# 8_-_DAC_and_MIC.net
KiCad netlist of a schematic drawn in Altium Designer
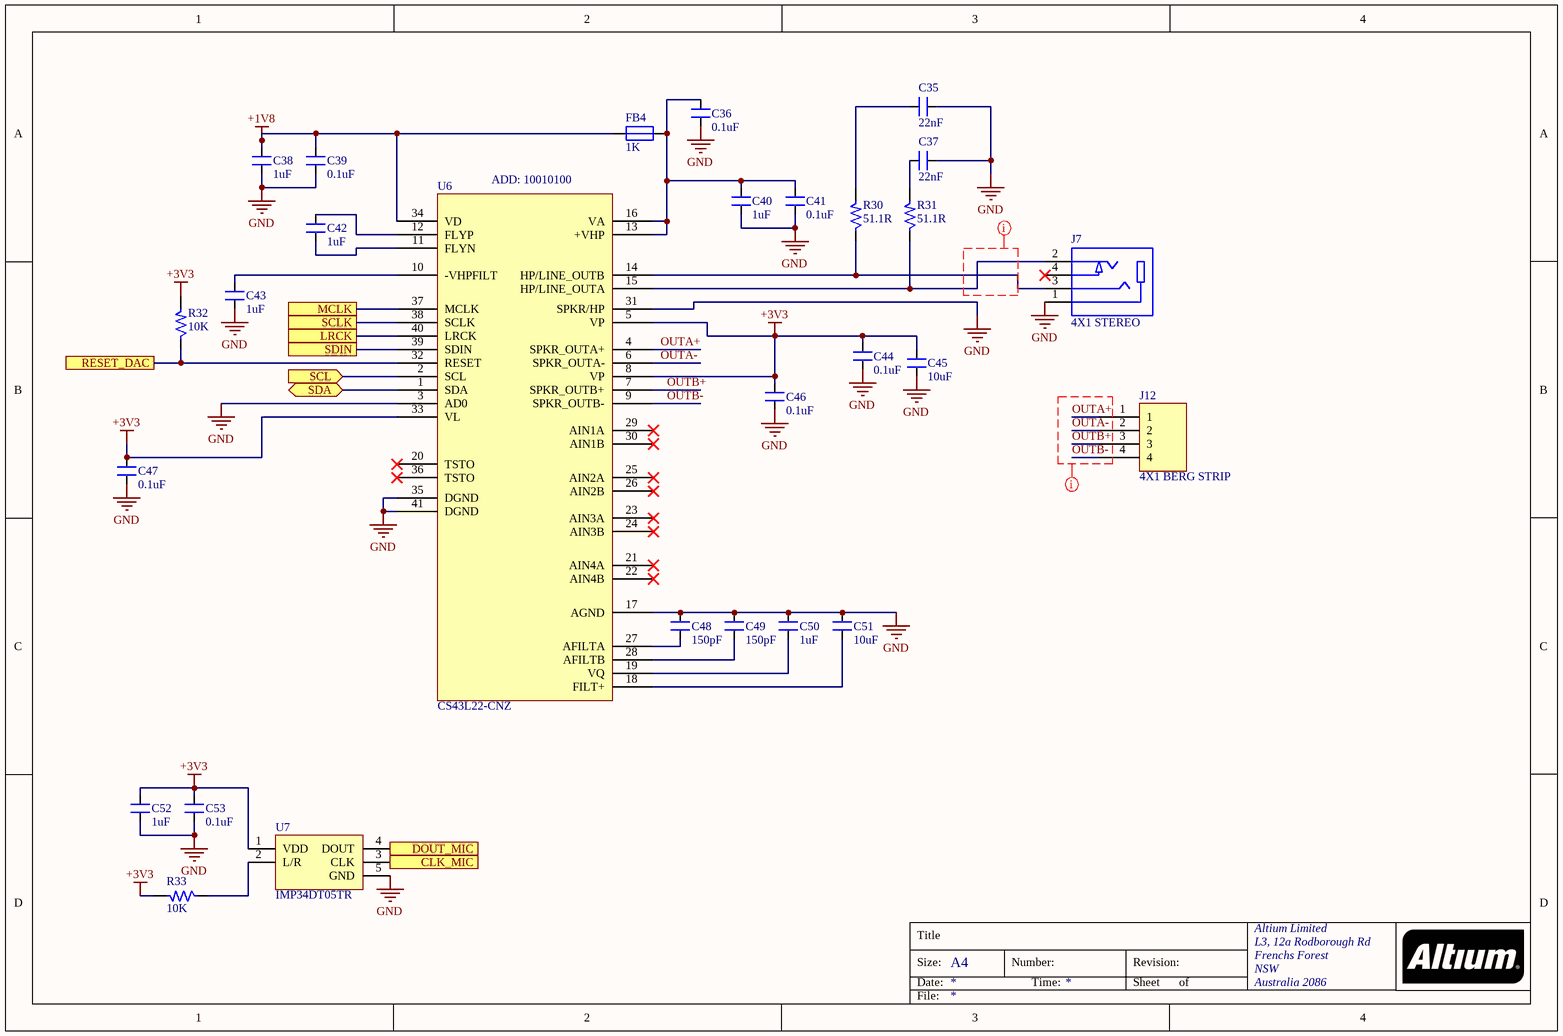
[diagram p0: [8] - DAC and MIC.SchDoc]

(export (version "E")
  (design (tool "Eeschema 10.0.6"))
  (components
    (comp (ref "C35")
      (value "22nF")
      (footprint "CAP_0805")
      (description "0.022µF ±10% 50V Ceramic Capacitor X7R 0805 (2012 Metric)")
      (fields
        (field (name "MANUFACTURER") "Samsung Electro-Mechanics")
        (field (name "MANUFACTURER PART NUMBER") "CL21B223KBANNNC")
      )
      (libsource (lib "ESTEEMPCBLIB") (part "CAP_22nF-50V-10%-0805"))
    )
    (comp (ref "C36")
      (value "0.1uF")
      (footprint "CAP_0805")
      (description "0.1µF ±10% 50V Ceramic Capacitor X7R 0805 (2012 Metric)")
      (fields
        (field (name "MANUFACTURER") "Samsung")
        (field (name "MANUFACTURER PART NUMBER") "CL21B104KBCNNNC")
      )
      (libsource (lib "ESTEEMPCBLIB") (part "CAP_0.1uF-50V-10%-0805"))
    )
    (comp (ref "C37")
      (value "22nF")
      (footprint "CAP_0805")
      (description "0.022µF ±10% 50V Ceramic Capacitor X7R 0805 (2012 Metric)")
      (fields
        (field (name "MANUFACTURER") "Samsung Electro-Mechanics")
        (field (name "MANUFACTURER PART NUMBER") "CL21B223KBANNNC")
      )
      (libsource (lib "ESTEEMPCBLIB") (part "CAP_22nF-50V-10%-0805"))
    )
    (comp (ref "C38")
      (value "1uF")
      (footprint "CAP_0805")
      (description "1µF ±5% 50V Ceramic Capacitor X7R 0805 (2012 Metric)")
      (fields
        (field (name "MANUFACTURER") "Samsung")
        (field (name "MANUFACTURER PART NUMBER") "CC0805JKX7R9BB105")
      )
      (libsource (lib "ESTEEMPCBLIB") (part "CAP_1uF-50V-5%-0805"))
    )
    (comp (ref "C39")
      (value "0.1uF")
      (footprint "CAP_0805")
      (description "0.1µF ±10% 50V Ceramic Capacitor X7R 0805 (2012 Metric)")
      (fields
        (field (name "MANUFACTURER") "Samsung")
        (field (name "MANUFACTURER PART NUMBER") "CL21B104KBCNNNC")
      )
      (libsource (lib "ESTEEMPCBLIB") (part "CAP_0.1uF-50V-10%-0805"))
    )
    (comp (ref "C40")
      (value "1uF")
      (footprint "CAP_0805")
      (description "1µF ±5% 50V Ceramic Capacitor X7R 0805 (2012 Metric)")
      (fields
        (field (name "MANUFACTURER") "Samsung")
        (field (name "MANUFACTURER PART NUMBER") "CC0805JKX7R9BB105")
      )
      (libsource (lib "ESTEEMPCBLIB") (part "CAP_1uF-50V-5%-0805"))
    )
    (comp (ref "C41")
      (value "0.1uF")
      (footprint "CAP_0805")
      (description "0.1µF ±10% 50V Ceramic Capacitor X7R 0805 (2012 Metric)")
      (fields
        (field (name "MANUFACTURER") "Samsung")
        (field (name "MANUFACTURER PART NUMBER") "CL21B104KBCNNNC")
      )
      (libsource (lib "ESTEEMPCBLIB") (part "CAP_0.1uF-50V-10%-0805"))
    )
    (comp (ref "C42")
      (value "1uF")
      (footprint "CAP_0805")
      (description "1µF ±5% 50V Ceramic Capacitor X7R 0805 (2012 Metric)")
      (fields
        (field (name "MANUFACTURER") "Samsung")
        (field (name "MANUFACTURER PART NUMBER") "CC0805JKX7R9BB105")
      )
      (libsource (lib "ESTEEMPCBLIB") (part "CAP_1uF-50V-5%-0805"))
    )
    (comp (ref "C43")
      (value "1uF")
      (footprint "CAP_0805")
      (description "1µF ±5% 50V Ceramic Capacitor X7R 0805 (2012 Metric)")
      (fields
        (field (name "MANUFACTURER") "Samsung")
        (field (name "MANUFACTURER PART NUMBER") "CC0805JKX7R9BB105")
      )
      (libsource (lib "ESTEEMPCBLIB") (part "CAP_1uF-50V-5%-0805"))
    )
    (comp (ref "C44")
      (value "0.1uF")
      (footprint "CAP_0805")
      (description "0.1µF ±10% 50V Ceramic Capacitor X7R 0805 (2012 Metric)")
      (fields
        (field (name "MANUFACTURER") "Samsung")
        (field (name "MANUFACTURER PART NUMBER") "CL21B104KBCNNNC")
      )
      (libsource (lib "ESTEEMPCBLIB") (part "CAP_0.1uF-50V-10%-0805"))
    )
    (comp (ref "C45")
      (value "10uF")
      (footprint "CAP_1206")
      (description "10µF ±10% 50V Ceramic Capacitor X7R 1206 (3216 Metric)")
      (fields
        (field (name "MANUFACTURER") "KEMET")
        (field (name "MANUFACTURER PART NUMBER") "CL31B106KBHNNNE")
      )
      (libsource (lib "ESTEEMPCBLIB") (part "CAP_10uF-50V-10%-1206"))
    )
    (comp (ref "C46")
      (value "0.1uF")
      (footprint "CAP_0805")
      (description "0.1µF ±10% 50V Ceramic Capacitor X7R 0805 (2012 Metric)")
      (fields
        (field (name "MANUFACTURER") "Samsung")
        (field (name "MANUFACTURER PART NUMBER") "CL21B104KBCNNNC")
      )
      (libsource (lib "ESTEEMPCBLIB") (part "CAP_0.1uF-50V-10%-0805"))
    )
    (comp (ref "C47")
      (value "0.1uF")
      (footprint "CAP_0805")
      (description "0.1µF ±10% 50V Ceramic Capacitor X7R 0805 (2012 Metric)")
      (fields
        (field (name "MANUFACTURER") "Samsung")
        (field (name "MANUFACTURER PART NUMBER") "CL21B104KBCNNNC")
      )
      (libsource (lib "ESTEEMPCBLIB") (part "CAP_0.1uF-50V-10%-0805"))
    )
    (comp (ref "C48")
      (value "150pF")
      (footprint "CAP_0805")
      (description "150pF ±10% 50V Ceramic Capacitor C0G, NP0 0805 (2012 Metric)")
      (fields
        (field (name "MANUFACTURER") "AVX Corporation")
        (field (name "MANUFACTURER PART NUMBER") "08055A151KAT2A")
      )
      (libsource (lib "ESTEEMPCBLIB") (part "CAP_150pF-50V-10%-0805"))
    )
    (comp (ref "C49")
      (value "150pF")
      (footprint "CAP_0805")
      (description "150pF ±10% 50V Ceramic Capacitor C0G, NP0 0805 (2012 Metric)")
      (fields
        (field (name "MANUFACTURER") "AVX Corporation")
        (field (name "MANUFACTURER PART NUMBER") "08055A151KAT2A")
      )
      (libsource (lib "ESTEEMPCBLIB") (part "CAP_150pF-50V-10%-0805"))
    )
    (comp (ref "C50")
      (value "1uF")
      (footprint "CAP_0805")
      (description "1µF ±5% 50V Ceramic Capacitor X7R 0805 (2012 Metric)")
      (fields
        (field (name "MANUFACTURER") "Samsung")
        (field (name "MANUFACTURER PART NUMBER") "CC0805JKX7R9BB105")
      )
      (libsource (lib "ESTEEMPCBLIB") (part "CAP_1uF-50V-5%-0805"))
    )
    (comp (ref "C51")
      (value "10uF")
      (footprint "CAP_1206")
      (description "10µF ±10% 50V Ceramic Capacitor X7R 1206 (3216 Metric)")
      (fields
        (field (name "MANUFACTURER") "KEMET")
        (field (name "MANUFACTURER PART NUMBER") "CL31B106KBHNNNE")
      )
      (libsource (lib "ESTEEMPCBLIB") (part "CAP_10uF-50V-10%-1206"))
    )
    (comp (ref "C52")
      (value "1uF")
      (footprint "CAP_0805")
      (description "1µF ±5% 50V Ceramic Capacitor X7R 0805 (2012 Metric)")
      (fields
        (field (name "MANUFACTURER") "Samsung")
        (field (name "MANUFACTURER PART NUMBER") "CC0805JKX7R9BB105")
      )
      (libsource (lib "ESTEEMPCBLIB") (part "CAP_1uF-50V-5%-0805"))
    )
    (comp (ref "C53")
      (value "0.1uF")
      (footprint "CAP_0805")
      (description "0.1µF ±10% 50V Ceramic Capacitor X7R 0805 (2012 Metric)")
      (fields
        (field (name "MANUFACTURER") "Samsung")
        (field (name "MANUFACTURER PART NUMBER") "CL21B104KBCNNNC")
      )
      (libsource (lib "ESTEEMPCBLIB") (part "CAP_0.1uF-50V-10%-0805"))
    )
    (comp (ref "FB4")
      (value "1K")
      (footprint "IND_0805")
      (description "1 kOhms @ 100MHz 1 Power Line Ferrite Bead 0805 (2012 Metric) 1.6A")
      (fields
        (field (name "MANUFACTURER") "Laird")
        (field (name "MANUFACTURER PART NUMBER") "BLM21SP102SH1D")
      )
      (libsource (lib "ESTEEMPCBLIB") (part "FB_1K-100MHZ-1.6A-0805"))
    )
    (comp (ref "J7")
      (value "4X1 STEREO")
      (footprint "CON_SJ-2504A-SMT-TR_SMD")
      (fields
        (field (name "MANUFACTURER") "CUI Devices")
        (field (name "MANUFACTURER PART NUMBER") "SJ-2504A-SMT-TR")
      )
      (libsource (lib "ESTEEMPCBLIB") (part "CON-PLG-STEREO_4X1-100-RA-SMD"))
    )
    (comp (ref "J12")
      (value "4X1 BERG STRIP")
      (footprint "CON4_100_40D72_TH_ST_MALE")
      (description "4 Pins, 1 Row 2.54mm Pitch, Straight bergstrip, Male")
      (fields (field (name "MANUFACTURER") "NA"))
      (libsource (lib "ESTEEMPCBLIB") (part "CON-BS-PLG_4X1-100-ST-TH"))
    )
    (comp (ref "R30")
      (value "51.1R")
      (footprint "RES_0603")
      (description "51.1 Ohms ±1% 0.1W, 1/10W Chip Resistor 0603 (1608 Metric) Thick Film")
      (fields
        (field (name "MANUFACTURER") "Vishay Dale")
        (field (name "MANUFACTURER PART NUMBER") "CRCW060351R1FKEAC")
      )
      (libsource (lib "ESTEEMPCBLIB") (part "RES_51.1R-0.1W-1%-0603"))
    )
    (comp (ref "R31")
      (value "51.1R")
      (footprint "RES_0603")
      (description "51.1 Ohms ±1% 0.1W, 1/10W Chip Resistor 0603 (1608 Metric) Thick Film")
      (fields
        (field (name "MANUFACTURER") "Vishay Dale")
        (field (name "MANUFACTURER PART NUMBER") "CRCW060351R1FKEAC")
      )
      (libsource (lib "ESTEEMPCBLIB") (part "RES_51.1R-0.1W-1%-0603"))
    )
    (comp (ref "R32")
      (value "10K")
      (footprint "RES_0805")
      (description "10 kOhms ±1% 0.125W, 1/8W Chip Resistor 0805 (2012 Metric) Automotive AEC-Q200 Thick Film")
      (fields (field (name "MANUFACTURER") "CTS") (field (name "MANUFACTURER PART NUMBER") "WR08X1002FTL"))
      (libsource (lib "ESTEEMPCBLIB") (part "RES_10K-0.125W-1%-0805"))
    )
    (comp (ref "R33")
      (value "10K")
      (footprint "RES_0805")
      (description "10 kOhms ±1% 0.125W, 1/8W Chip Resistor 0805 (2012 Metric) Automotive AEC-Q200 Thick Film")
      (fields (field (name "MANUFACTURER") "CTS") (field (name "MANUFACTURER PART NUMBER") "WR08X1002FTL"))
      (libsource (lib "ESTEEMPCBLIB") (part "RES_10K-0.125W-1%-0805"))
    )
    (comp (ref "U6")
      (value "CS43L22-CNZ")
      (footprint "QFN40_19_284_33X9_SMD")
      (description "Audio D/A Converter ICs Low Power Stereo DAC w/ClassD Spkr Driver")
      (fields (field (name "MANUFACTURER") "Cirrus Logic"))
      (libsource (lib "ESTEEMPCBLIB") (part "IC_CS43L22"))
    )
    (comp (ref "U7")
      (value "IMP34DT05TR")
      (footprint "HCLGA-4_53_137_15X37_SMD")
      (description "MEMS Microphones AUTO & INDUSTRIAL SENSORS")
      (fields (field (name "MANUFACTURER") "STMicroelectronics"))
      (libsource (lib "ESTEEMPCBLIB") (part "IC_IMP34DT05TR"))
    )
  )
  (nets
    (net (code "1") (name "+1V8") (class "Default")
      (node (ref "C38") (pin "1") (pinfunction "1_1") (pintype "passive"))
      (node (ref "C39") (pin "2") (pinfunction "2_2") (pintype "passive"))
      (node (ref "FB4") (pin "1") (pinfunction "1_1") (pintype "passive"))
      (node (ref "U6") (pin "34") (pinfunction "VD_34") (pintype "passive"))
    )
    (net (code "2") (name "+3V3") (class "Default")
      (node (ref "C44") (pin "2") (pinfunction "2_2") (pintype "passive"))
      (node (ref "C45") (pin "2") (pinfunction "2_2") (pintype "passive"))
      (node (ref "C46") (pin "2") (pinfunction "2_2") (pintype "passive"))
      (node (ref "C47") (pin "2") (pinfunction "2_2") (pintype "passive"))
      (node (ref "C52") (pin "1") (pinfunction "1_1") (pintype "passive"))
      (node (ref "C53") (pin "2") (pinfunction "2_2") (pintype "passive"))
      (node (ref "R32") (pin "2") (pinfunction "2_2") (pintype "passive"))
      (node (ref "R33") (pin "2") (pinfunction "2_2") (pintype "passive"))
      (node (ref "U6") (pin "33") (pinfunction "VL_33") (pintype "passive"))
      (node (ref "U6") (pin "5") (pinfunction "VP_5") (pintype "passive"))
      (node (ref "U6") (pin "8") (pinfunction "VP_8") (pintype "passive"))
      (node (ref "U7") (pin "1") (pinfunction "VDD_1") (pintype "passive"))
    )
    (net (code "3") (name "/CLK_MIC") (class "Default")
      (node (ref "U7") (pin "3") (pinfunction "CLK_3") (pintype "passive"))
    )
    (net (code "4") (name "/DOUT_MIC") (class "Default")
      (node (ref "U7") (pin "4") (pinfunction "DOUT_4") (pintype "passive"))
    )
    (net (code "5") (name "/LRCK") (class "Default")
      (node (ref "U6") (pin "40") (pinfunction "LRCK_40") (pintype "passive"))
    )
    (net (code "6") (name "/MCLK") (class "Default")
      (node (ref "U6") (pin "37") (pinfunction "MCLK_37") (pintype "passive"))
    )
    (net (code "7") (name "/OUTA+") (class "Default")
      (node (ref "J12") (pin "1") (pinfunction "1_1") (pintype "passive"))
      (node (ref "U6") (pin "4") (pinfunction "SPKR_OUTA+_4") (pintype "passive"))
    )
    (net (code "8") (name "/OUTA-") (class "Default")
      (node (ref "J12") (pin "2") (pinfunction "2_2") (pintype "passive"))
      (node (ref "U6") (pin "6") (pinfunction "SPKR_OUTA-_6") (pintype "passive"))
    )
    (net (code "9") (name "/OUTB+") (class "Default")
      (node (ref "J12") (pin "3") (pinfunction "3_3") (pintype "passive"))
      (node (ref "U6") (pin "7") (pinfunction "SPKR_OUTB+_7") (pintype "passive"))
    )
    (net (code "10") (name "/OUTB-") (class "Default")
      (node (ref "J12") (pin "4") (pinfunction "4_4") (pintype "passive"))
      (node (ref "U6") (pin "9") (pinfunction "SPKR_OUTB-_9") (pintype "passive"))
    )
    (net (code "11") (name "/RESET_DAC") (class "Default")
      (node (ref "R32") (pin "1") (pinfunction "1_1") (pintype "passive"))
      (node (ref "U6") (pin "32") (pinfunction "RESET_32") (pintype "passive"))
    )
    (net (code "12") (name "/SCL") (class "Default")
      (node (ref "U6") (pin "2") (pinfunction "SCL_2") (pintype "passive"))
    )
    (net (code "13") (name "/SCLK") (class "Default")
      (node (ref "U6") (pin "38") (pinfunction "SCLK_38") (pintype "passive"))
    )
    (net (code "14") (name "/SDA") (class "Default")
      (node (ref "U6") (pin "1") (pinfunction "SDA_1") (pintype "passive"))
    )
    (net (code "15") (name "/SDIN") (class "Default")
      (node (ref "U6") (pin "39") (pinfunction "SDIN_39") (pintype "passive"))
    )
    (net (code "16") (name "GND") (class "Default")
      (node (ref "C35") (pin "2") (pinfunction "2_2") (pintype "passive"))
      (node (ref "C36") (pin "1") (pinfunction "1_1") (pintype "passive"))
      (node (ref "C37") (pin "2") (pinfunction "2_2") (pintype "passive"))
      (node (ref "C38") (pin "2") (pinfunction "2_2") (pintype "passive"))
      (node (ref "C39") (pin "1") (pinfunction "1_1") (pintype "passive"))
      (node (ref "C40") (pin "2") (pinfunction "2_2") (pintype "passive"))
      (node (ref "C41") (pin "1") (pinfunction "1_1") (pintype "passive"))
      (node (ref "C43") (pin "2") (pinfunction "2_2") (pintype "passive"))
      (node (ref "C44") (pin "1") (pinfunction "1_1") (pintype "passive"))
      (node (ref "C45") (pin "1") (pinfunction "1_1") (pintype "passive"))
      (node (ref "C46") (pin "1") (pinfunction "1_1") (pintype "passive"))
      (node (ref "C47") (pin "1") (pinfunction "1_1") (pintype "passive"))
      (node (ref "C48") (pin "2") (pinfunction "2_2") (pintype "passive"))
      (node (ref "C49") (pin "2") (pinfunction "2_2") (pintype "passive"))
      (node (ref "C50") (pin "1") (pinfunction "1_1") (pintype "passive"))
      (node (ref "C51") (pin "2") (pinfunction "2_2") (pintype "passive"))
      (node (ref "C52") (pin "2") (pinfunction "2_2") (pintype "passive"))
      (node (ref "C53") (pin "1") (pinfunction "1_1") (pintype "passive"))
      (node (ref "J7") (pin "1") (pinfunction "1_1") (pintype "passive"))
      (node (ref "U6") (pin "17") (pinfunction "AGND_17") (pintype "passive"))
      (node (ref "U6") (pin "3") (pinfunction "AD0_3") (pintype "passive"))
      (node (ref "U6") (pin "31") (pinfunction "SPKR/HP_31") (pintype "passive"))
      (node (ref "U6") (pin "35") (pinfunction "DGND_35") (pintype "passive"))
      (node (ref "U6") (pin "41") (pinfunction "DGND_41") (pintype "passive"))
      (node (ref "U7") (pin "5") (pinfunction "GND_5") (pintype "passive"))
    )
    (net (code "17") (name "Net-(C35-Pad1)") (class "Default")
      (node (ref "C35") (pin "1") (pinfunction "1_1") (pintype "passive"))
      (node (ref "R30") (pin "2") (pinfunction "2_2") (pintype "passive"))
    )
    (net (code "18") (name "Net-(C37-Pad1)") (class "Default")
      (node (ref "C37") (pin "1") (pinfunction "1_1") (pintype "passive"))
      (node (ref "R31") (pin "2") (pinfunction "2_2") (pintype "passive"))
    )
    (net (code "19") (name "Net-(U6-+VHP)") (class "Default")
      (node (ref "C36") (pin "2") (pinfunction "2_2") (pintype "passive"))
      (node (ref "C40") (pin "1") (pinfunction "1_1") (pintype "passive"))
      (node (ref "C41") (pin "2") (pinfunction "2_2") (pintype "passive"))
      (node (ref "FB4") (pin "2") (pinfunction "2_2") (pintype "passive"))
      (node (ref "U6") (pin "13") (pinfunction "+VHP_13") (pintype "passive"))
      (node (ref "U6") (pin "16") (pinfunction "VA_16") (pintype "passive"))
    )
    (net (code "20") (name "Net-(U6--VHPFILT)") (class "Default")
      (node (ref "C43") (pin "1") (pinfunction "1_1") (pintype "passive"))
      (node (ref "U6") (pin "10") (pinfunction "-VHPFILT_10") (pintype "passive"))
    )
    (net (code "21") (name "Net-(U6-AFILTA)") (class "Default")
      (node (ref "C48") (pin "1") (pinfunction "1_1") (pintype "passive"))
      (node (ref "U6") (pin "27") (pinfunction "AFILTA_27") (pintype "passive"))
    )
    (net (code "22") (name "Net-(U6-AFILTB)") (class "Default")
      (node (ref "C49") (pin "1") (pinfunction "1_1") (pintype "passive"))
      (node (ref "U6") (pin "28") (pinfunction "AFILTB_28") (pintype "passive"))
    )
    (net (code "23") (name "Net-(U6-FILT+)") (class "Default")
      (node (ref "C51") (pin "1") (pinfunction "1_1") (pintype "passive"))
      (node (ref "U6") (pin "18") (pinfunction "FILT+_18") (pintype "passive"))
    )
    (net (code "24") (name "Net-(U6-FLYN)") (class "Default")
      (node (ref "C42") (pin "2") (pinfunction "2_2") (pintype "passive"))
      (node (ref "U6") (pin "11") (pinfunction "FLYN_11") (pintype "passive"))
    )
    (net (code "25") (name "Net-(U6-FLYP)") (class "Default")
      (node (ref "C42") (pin "1") (pinfunction "1_1") (pintype "passive"))
      (node (ref "U6") (pin "12") (pinfunction "FLYP_12") (pintype "passive"))
    )
    (net (code "26") (name "Net-(U6-HP{slash}LINE_OUTA)") (class "Default")
      (node (ref "J7") (pin "2") (pinfunction "2_2") (pintype "passive"))
      (node (ref "R31") (pin "1") (pinfunction "1_1") (pintype "passive"))
      (node (ref "U6") (pin "15") (pinfunction "HP/LINE_OUTA_15") (pintype "passive"))
    )
    (net (code "27") (name "Net-(U6-HP{slash}LINE_OUTB)") (class "Default")
      (node (ref "J7") (pin "3") (pinfunction "3_3") (pintype "passive"))
      (node (ref "R30") (pin "1") (pinfunction "1_1") (pintype "passive"))
      (node (ref "U6") (pin "14") (pinfunction "HP/LINE_OUTB_14") (pintype "passive"))
    )
    (net (code "28") (name "Net-(U6-VQ)") (class "Default")
      (node (ref "C50") (pin "2") (pinfunction "2_2") (pintype "passive"))
      (node (ref "U6") (pin "19") (pinfunction "VQ_19") (pintype "passive"))
    )
    (net (code "29") (name "Net-(U7-L{slash}R)") (class "Default")
      (node (ref "R33") (pin "1") (pinfunction "1_1") (pintype "passive"))
      (node (ref "U7") (pin "2") (pinfunction "L/R_2") (pintype "passive"))
    )
    (net (code "30") (name "unconnected-(J7-Pad4)") (class "Default")
      (node (ref "J7") (pin "4") (pinfunction "4_4") (pintype "passive+no_connect"))
    )
    (net (code "31") (name "unconnected-(U6-AIN1A-Pad29)") (class "Default")
      (node (ref "U6") (pin "29") (pinfunction "AIN1A_29") (pintype "passive+no_connect"))
    )
    (net (code "32") (name "unconnected-(U6-AIN1B-Pad30)") (class "Default")
      (node (ref "U6") (pin "30") (pinfunction "AIN1B_30") (pintype "passive+no_connect"))
    )
    (net (code "33") (name "unconnected-(U6-AIN2A-Pad25)") (class "Default")
      (node (ref "U6") (pin "25") (pinfunction "AIN2A_25") (pintype "passive+no_connect"))
    )
    (net (code "34") (name "unconnected-(U6-AIN2B-Pad26)") (class "Default")
      (node (ref "U6") (pin "26") (pinfunction "AIN2B_26") (pintype "passive+no_connect"))
    )
    (net (code "35") (name "unconnected-(U6-AIN3A-Pad23)") (class "Default")
      (node (ref "U6") (pin "23") (pinfunction "AIN3A_23") (pintype "passive+no_connect"))
    )
    (net (code "36") (name "unconnected-(U6-AIN3B-Pad24)") (class "Default")
      (node (ref "U6") (pin "24") (pinfunction "AIN3B_24") (pintype "passive+no_connect"))
    )
    (net (code "37") (name "unconnected-(U6-AIN4A-Pad21)") (class "Default")
      (node (ref "U6") (pin "21") (pinfunction "AIN4A_21") (pintype "passive+no_connect"))
    )
    (net (code "38") (name "unconnected-(U6-AIN4B-Pad22)") (class "Default")
      (node (ref "U6") (pin "22") (pinfunction "AIN4B_22") (pintype "passive+no_connect"))
    )
    (net (code "39") (name "unconnected-(U6-TSTO-Pad20)") (class "Default")
      (node (ref "U6") (pin "20") (pinfunction "TSTO_20") (pintype "passive+no_connect"))
    )
    (net (code "40") (name "unconnected-(U6-TSTO-Pad36)") (class "Default")
      (node (ref "U6") (pin "36") (pinfunction "TSTO_36") (pintype "passive+no_connect"))
    )
  )
)
